# usbttl.net
KiCad netlist of a schematic drawn in Altium Designer
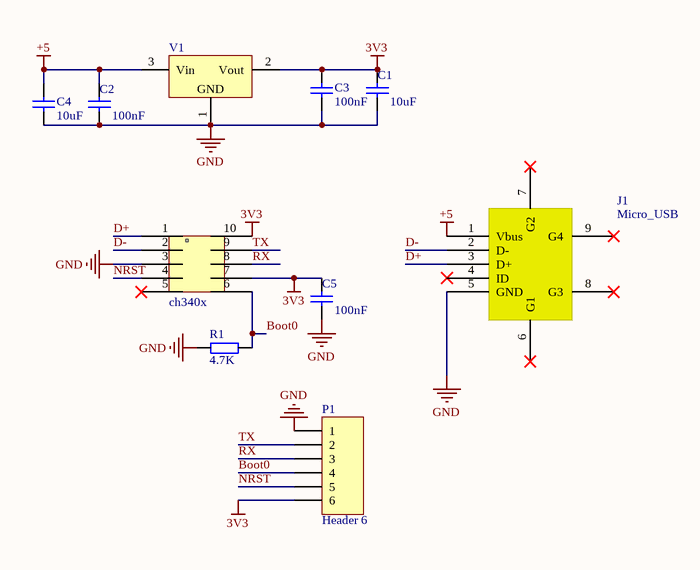
[diagram p0: usbttl.SchDoc]

(export (version "E")
  (design (tool "Eeschema 10.0.6"))
  (components
    (comp (ref "*1")
      (value "ch340x")
      (footprint "MSOP-10_L3.0-W3.0-P0.50-LS5.0-BL")
      (libsource (lib "常用元件库") (part "ch340x"))
    )
    (comp (ref "C1")
      (value "10uF")
      (footprint "C0603")
      (description "Capacitor")
      (fields (field (name "PUBLISHER") "Altium Limited"))
      (libsource (lib "Miscellaneous Devices") (part "Cap"))
    )
    (comp (ref "C2")
      (value "100nF")
      (footprint "C0603")
      (description "Capacitor")
      (fields (field (name "PUBLISHER") "Altium Limited"))
      (libsource (lib "Miscellaneous Devices") (part "Cap"))
    )
    (comp (ref "C3")
      (value "100nF")
      (footprint "C0603")
      (description "Capacitor")
      (fields (field (name "PUBLISHER") "Altium Limited"))
      (libsource (lib "Miscellaneous Devices") (part "Cap"))
    )
    (comp (ref "C4")
      (value "10uF")
      (footprint "C0603")
      (description "Capacitor")
      (fields (field (name "PUBLISHER") "Altium Limited"))
      (libsource (lib "Miscellaneous Devices") (part "Cap"))
    )
    (comp (ref "C5")
      (value "100nF")
      (footprint "C0603")
      (description "Capacitor")
      (fields (field (name "PUBLISHER") "Altium Limited"))
      (libsource (lib "Miscellaneous Devices") (part "Cap"))
    )
    (comp (ref "J1")
      (value "Micro_USB")
      (footprint "MICRO-USB-SMD_MICROQTJ")
      (libsource (lib "Dr.Xiong_20160818") (part "Micro_USB"))
    )
    (comp (ref "P1")
      (value "Header 6")
      (footprint "HDR-TH_6P-P2.54-V-M-R2-C3-S2.54-1")
      (description "Header, 6-Pin")
      (fields (field (name "PUBLISHER") "Altium Limited"))
      (libsource (lib "Miscellaneous Connectors") (part "Header 6"))
    )
    (comp (ref "R1") (value "4.7K") (footprint "0603P") (libsource (lib "朱雀F103开发板封装库") (part "R")))
    (comp (ref "V1")
      (value "AMS1117-3V3")
      (footprint "SOT223_L")
      (description "三端稳压芯片")
      (fields (field (name "版权归属") "源创客"))
      (libsource (lib "1.3   - 电源类芯片") (part "AMS1117"))
    )
  )
  (nets
    (net (code "1") (name "+5") (class "Default")
      (node (ref "C2") (pin "2") (pinfunction "2_2") (pintype "passive"))
      (node (ref "C4") (pin "2") (pinfunction "2_2") (pintype "passive"))
      (node (ref "J1") (pin "1") (pinfunction "Vbus_1") (pintype "passive"))
      (node (ref "V1") (pin "3") (pinfunction "Vin_3") (pintype "passive"))
    )
    (net (code "2") (name "/Boot0") (class "Default")
      (node (ref "*1") (pin "6") (pinfunction "DTR#_6") (pintype "passive"))
      (node (ref "P1") (pin "4") (pinfunction "4_4") (pintype "passive"))
      (node (ref "R1") (pin "2") (pintype "passive"))
    )
    (net (code "3") (name "/D+") (class "Default")
      (node (ref "*1") (pin "1") (pinfunction "UD+_1") (pintype "passive"))
      (node (ref "J1") (pin "3") (pinfunction "D+_3") (pintype "passive"))
    )
    (net (code "4") (name "/D-") (class "Default")
      (node (ref "*1") (pin "2") (pinfunction "UD-_2") (pintype "passive"))
      (node (ref "J1") (pin "2") (pinfunction "D-_2") (pintype "passive"))
    )
    (net (code "5") (name "/NRST") (class "Default")
      (node (ref "*1") (pin "4") (pinfunction "RTS#_4") (pintype "passive"))
      (node (ref "P1") (pin "5") (pinfunction "5_5") (pintype "passive"))
    )
    (net (code "6") (name "/RX") (class "Default")
      (node (ref "*1") (pin "8") (pinfunction "TXD_8") (pintype "passive"))
      (node (ref "P1") (pin "3") (pinfunction "3_3") (pintype "passive"))
    )
    (net (code "7") (name "/TX") (class "Default")
      (node (ref "*1") (pin "9") (pinfunction "RXD_9") (pintype "passive"))
      (node (ref "P1") (pin "2") (pinfunction "2_2") (pintype "passive"))
    )
    (net (code "8") (name "3V3") (class "Default")
      (node (ref "*1") (pin "10") (pinfunction "V3_10") (pintype "passive"))
      (node (ref "*1") (pin "7") (pinfunction "VCC_7") (pintype "passive"))
      (node (ref "C1") (pin "2") (pinfunction "2_2") (pintype "passive"))
      (node (ref "C3") (pin "2") (pinfunction "2_2") (pintype "passive"))
      (node (ref "C5") (pin "2") (pinfunction "2_2") (pintype "passive"))
      (node (ref "P1") (pin "6") (pinfunction "6_6") (pintype "passive"))
      (node (ref "V1") (pin "2") (pinfunction "Vout_2") (pintype "passive"))
    )
    (net (code "9") (name "GND") (class "Default")
      (node (ref "*1") (pin "3") (pinfunction "GND_3") (pintype "passive"))
      (node (ref "C1") (pin "1") (pinfunction "1_1") (pintype "passive"))
      (node (ref "C2") (pin "1") (pinfunction "1_1") (pintype "passive"))
      (node (ref "C3") (pin "1") (pinfunction "1_1") (pintype "passive"))
      (node (ref "C4") (pin "1") (pinfunction "1_1") (pintype "passive"))
      (node (ref "C5") (pin "1") (pinfunction "1_1") (pintype "passive"))
      (node (ref "J1") (pin "5") (pinfunction "GND_5") (pintype "passive"))
      (node (ref "P1") (pin "1") (pinfunction "1_1") (pintype "passive"))
      (node (ref "R1") (pin "1") (pintype "passive"))
      (node (ref "V1") (pin "1") (pinfunction "GND_1") (pintype "passive"))
    )
    (net (code "10") (name "unconnected-(*1-CTS#-Pad5)") (class "Default")
      (node (ref "*1") (pin "5") (pinfunction "CTS#_5") (pintype "passive+no_connect"))
    )
    (net (code "11") (name "unconnected-(J1-G1-Pad6)") (class "Default")
      (node (ref "J1") (pin "6") (pinfunction "G1_6") (pintype "passive+no_connect"))
    )
    (net (code "12") (name "unconnected-(J1-G2-Pad7)") (class "Default")
      (node (ref "J1") (pin "7") (pinfunction "G2_7") (pintype "passive+no_connect"))
    )
    (net (code "13") (name "unconnected-(J1-G3-Pad8)") (class "Default")
      (node (ref "J1") (pin "8") (pinfunction "G3_8") (pintype "passive+no_connect"))
    )
    (net (code "14") (name "unconnected-(J1-G4-Pad9)") (class "Default")
      (node (ref "J1") (pin "9") (pinfunction "G4_9") (pintype "passive+no_connect"))
    )
    (net (code "15") (name "unconnected-(J1-ID-Pad4)") (class "Default")
      (node (ref "J1") (pin "4") (pinfunction "ID_4") (pintype "passive+no_connect"))
    )
  )
)
